# Shield_PCB.net
KiCad netlist of a schematic drawn in EAGLE
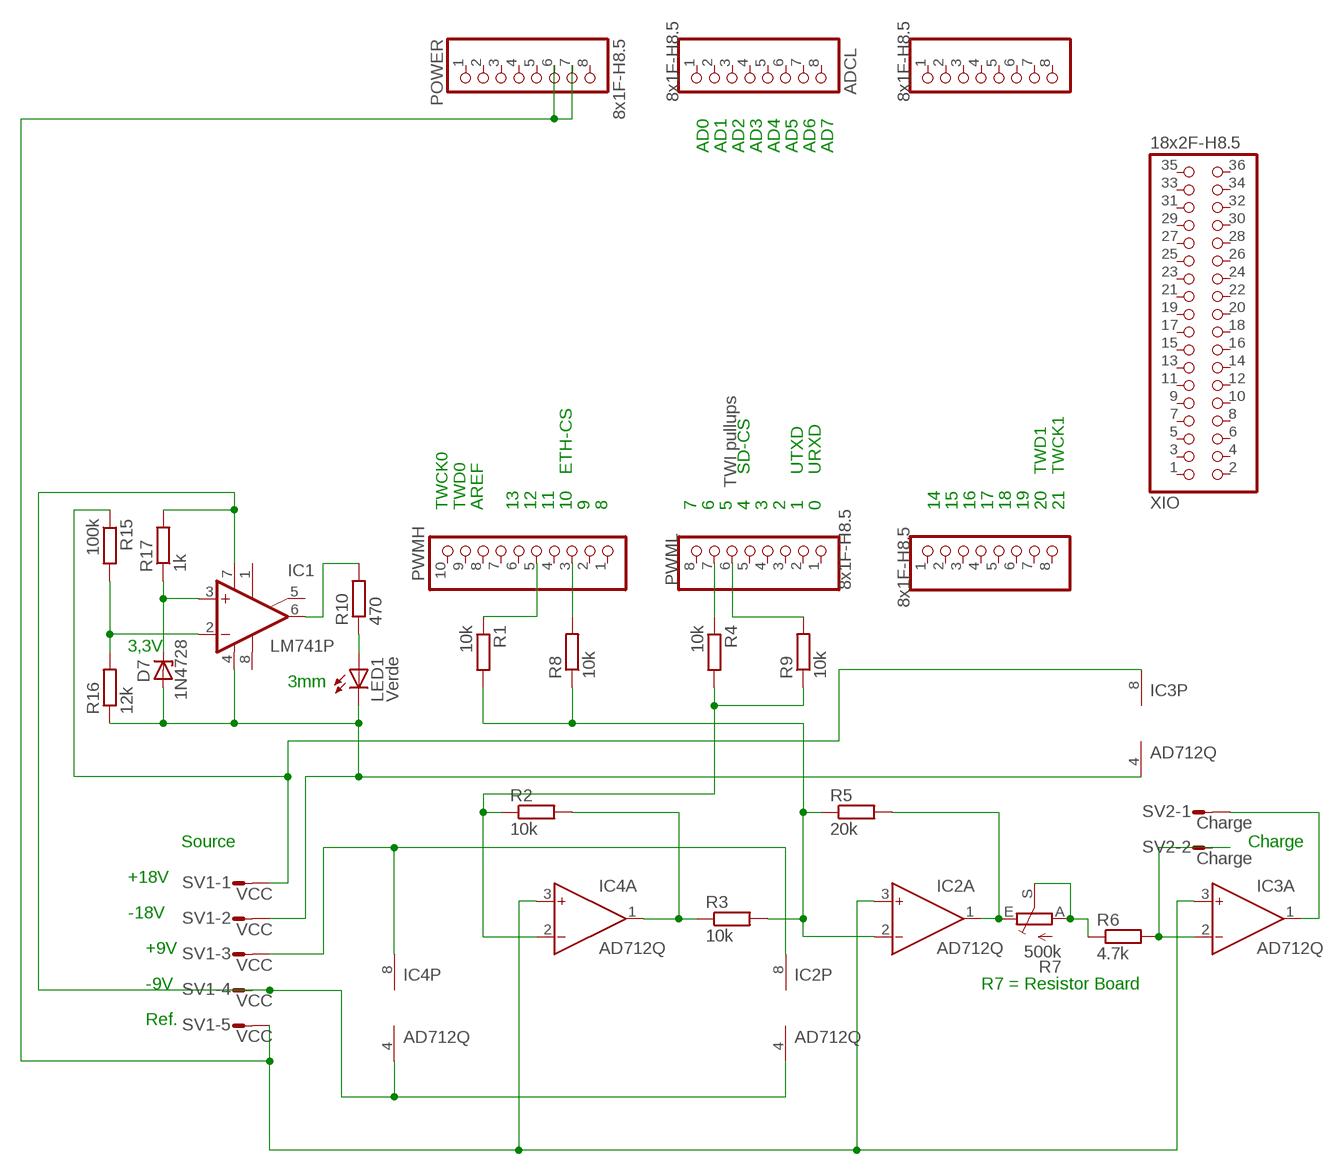
[diagram p0: schematic, sheet 1]

(export (version "E")
  (design (tool "Eeschema 10.0.6"))
  (components
    (comp (ref "ADCH")
      (value "8x1F-H8.5")
      (footprint "eagle-import:1X08")
      (libsource (lib "eagle-import") (part "PINHD-1X8"))
    )
    (comp (ref "ADCL")
      (value "8x1F-H8.5")
      (footprint "eagle-import:1X08")
      (libsource (lib "eagle-import") (part "PINHD-1X8"))
    )
    (comp (ref "COMMUNICATION")
      (value "8x1F-H8.5")
      (footprint "eagle-import:1X08")
      (libsource (lib "eagle-import") (part "PINHD-1X8"))
    )
    (comp (ref "D7")
      (value "1N4728")
      (footprint "eagle-import:DO41Z10")
      (libsource (lib "eagle-import") (part "1N4728"))
    )
    (comp (ref "IC1")
      (value "LM741P")
      (footprint "eagle-import:DIL08")
      (libsource (lib "eagle-import") (part "741PLM"))
    )
    (comp (ref "IC2")
      (value "AD712Q")
      (footprint "eagle-import:DIL08")
      (fields (field (name "MF") "ALTERA CORPORATION") (field (name "MPN") "AD712AQ"))
      (libsource (lib "eagle-import") (part "AD712Q"))
    )
    (comp (ref "IC3")
      (value "AD712Q")
      (footprint "eagle-import:DIL08")
      (fields (field (name "MF") "ALTERA CORPORATION") (field (name "MPN") "AD712AQ"))
      (libsource (lib "eagle-import") (part "AD712Q"))
    )
    (comp (ref "IC4")
      (value "AD712Q")
      (footprint "eagle-import:DIL08")
      (fields (field (name "MF") "ALTERA CORPORATION") (field (name "MPN") "AD712AQ"))
      (libsource (lib "eagle-import") (part "AD712Q"))
    )
    (comp (ref "LED1")
      (value "Verde")
      (footprint "eagle-import:LED3MM")
      (libsource (lib "eagle-import") (part "LED3MM"))
    )
    (comp (ref "POWER")
      (value "8x1F-H8.5")
      (footprint "eagle-import:1X08")
      (libsource (lib "eagle-import") (part "PINHD-1X8"))
    )
    (comp (ref "PWMH")
      (value "10x1F-H8.5")
      (footprint "eagle-import:1X10")
      (libsource (lib "eagle-import") (part "PINHD-1X10"))
    )
    (comp (ref "PWML")
      (value "8x1F-H8.5")
      (footprint "eagle-import:1X08")
      (libsource (lib "eagle-import") (part "PINHD-1X8"))
    )
    (comp (ref "R1")
      (value "10k")
      (footprint "eagle-import:0207_10")
      (libsource (lib "eagle-import") (part "resistor_R-EU_0207/10"))
    )
    (comp (ref "R2")
      (value "10k")
      (footprint "eagle-import:0207_10")
      (libsource (lib "eagle-import") (part "resistor_R-EU_0207/10"))
    )
    (comp (ref "R3")
      (value "10k")
      (footprint "eagle-import:0207_10")
      (libsource (lib "eagle-import") (part "resistor_R-EU_0207/10"))
    )
    (comp (ref "R4")
      (value "10k")
      (footprint "eagle-import:0207_10")
      (libsource (lib "eagle-import") (part "resistor_R-EU_0207/10"))
    )
    (comp (ref "R5")
      (value "20k")
      (footprint "eagle-import:0207_10")
      (libsource (lib "eagle-import") (part "resistor_R-EU_0207/10"))
    )
    (comp (ref "R6")
      (value "4.7k")
      (footprint "eagle-import:0207_10")
      (libsource (lib "eagle-import") (part "R-EU_0207/10"))
    )
    (comp (ref "R7")
      (value "500k")
      (footprint "eagle-import:B64Y")
      (libsource (lib "eagle-import") (part "TRIM_EU-B64Y"))
    )
    (comp (ref "R8")
      (value "10k")
      (footprint "eagle-import:0207_10")
      (libsource (lib "eagle-import") (part "resistor_R-EU_0207/10"))
    )
    (comp (ref "R9")
      (value "10k")
      (footprint "eagle-import:0207_10")
      (libsource (lib "eagle-import") (part "resistor_R-EU_0207/10"))
    )
    (comp (ref "R10")
      (value "470")
      (footprint "eagle-import:0207_10")
      (libsource (lib "eagle-import") (part "resistor_R-EU_0207/10"))
    )
    (comp (ref "R15")
      (value "100k")
      (footprint "eagle-import:0207_10")
      (libsource (lib "eagle-import") (part "resistor_R-EU_0207/10"))
    )
    (comp (ref "R16")
      (value "12k")
      (footprint "eagle-import:0207_10")
      (libsource (lib "eagle-import") (part "resistor_R-EU_0207/10"))
    )
    (comp (ref "R17")
      (value "1k")
      (footprint "eagle-import:0207_10")
      (libsource (lib "eagle-import") (part "resistor_R-EU_0207/10"))
    )
    (comp (ref "SV1")
      (value "VCC")
      (footprint "eagle-import:L05P")
      (libsource (lib "eagle-import") (part "L05P"))
    )
    (comp (ref "SV2")
      (value "Charge")
      (footprint "eagle-import:L02P")
      (libsource (lib "eagle-import") (part "L02P"))
    )
    (comp (ref "XIO")
      (value "18x2F-H8.5")
      (footprint "eagle-import:2X18")
      (libsource (lib "eagle-import") (part "PINHD-2X18"))
    )
  )
  (nets
    (net (code "1") (name "Net-(IC1-+IN)") (class "Default")
      (node (ref "D7") (pin "C") (pinfunction "C_C") (pintype "passive"))
      (node (ref "IC1") (pin "3") (pinfunction "+IN_3") (pintype "input"))
      (node (ref "R17") (pin "1") (pinfunction "1_1") (pintype "passive"))
    )
    (net (code "2") (name "Net-(IC1--IN)") (class "Default")
      (node (ref "IC1") (pin "2") (pinfunction "-IN_2") (pintype "input"))
      (node (ref "R15") (pin "2") (pinfunction "2_2") (pintype "passive"))
      (node (ref "R16") (pin "2") (pinfunction "2_2") (pintype "passive"))
    )
    (net (code "3") (name "Net-(IC1-OUT)") (class "Default")
      (node (ref "IC1") (pin "6") (pinfunction "OUT_6") (pintype "output"))
      (node (ref "R10") (pin "2") (pinfunction "2_2") (pintype "passive"))
    )
    (net (code "4") (name "Net-(IC1-V+)") (class "Default")
      (node (ref "IC1") (pin "7") (pinfunction "V+_7") (pintype "power_in"))
      (node (ref "IC2") (pin "4") (pinfunction "V-_4") (pintype "power_in"))
      (node (ref "IC4") (pin "4") (pinfunction "V-_4") (pintype "power_in"))
      (node (ref "R17") (pin "2") (pinfunction "2_2") (pintype "passive"))
      (node (ref "SV1") (pin "4") (pinfunction "S_4") (pintype "passive"))
    )
    (net (code "5") (name "Net-(IC1-V-)") (class "Default")
      (node (ref "D7") (pin "A") (pinfunction "A_A") (pintype "passive"))
      (node (ref "IC1") (pin "4") (pinfunction "V-_4") (pintype "power_in"))
      (node (ref "IC3") (pin "4") (pinfunction "V-_4") (pintype "power_in"))
      (node (ref "LED1") (pin "K") (pinfunction "C_K") (pintype "passive"))
      (node (ref "R16") (pin "1") (pinfunction "1_1") (pintype "passive"))
      (node (ref "SV1") (pin "2") (pinfunction "S_2") (pintype "passive"))
    )
    (net (code "6") (name "Net-(IC2A-IN+)") (class "Default")
      (node (ref "IC2") (pin "3") (pinfunction "IN+_3") (pintype "input"))
      (node (ref "IC3") (pin "3") (pinfunction "IN+_3") (pintype "input"))
      (node (ref "IC4") (pin "3") (pinfunction "IN+_3") (pintype "input"))
      (node (ref "POWER") (pin "6") (pinfunction "6_6") (pintype "passive"))
      (node (ref "POWER") (pin "7") (pinfunction "7_7") (pintype "passive"))
      (node (ref "SV1") (pin "5") (pinfunction "S_5") (pintype "passive"))
    )
    (net (code "7") (name "Net-(IC2A-IN-)") (class "Default")
      (node (ref "IC2") (pin "2") (pinfunction "IN-_2") (pintype "input"))
      (node (ref "R1") (pin "2") (pinfunction "2_2") (pintype "passive"))
      (node (ref "R3") (pin "2") (pinfunction "2_2") (pintype "passive"))
      (node (ref "R5") (pin "1") (pinfunction "1_1") (pintype "passive"))
      (node (ref "R8") (pin "1") (pinfunction "1_1") (pintype "passive"))
    )
    (net (code "8") (name "Net-(IC2A-OUT)") (class "Default")
      (node (ref "IC2") (pin "1") (pinfunction "OUT_1") (pintype "output"))
      (node (ref "R5") (pin "2") (pinfunction "2_2") (pintype "passive"))
      (node (ref "R7") (pin "E") (pinfunction "E_E") (pintype "passive"))
    )
    (net (code "9") (name "Net-(IC2C-V+)") (class "Default")
      (node (ref "IC2") (pin "8") (pinfunction "V+_8") (pintype "power_in"))
      (node (ref "IC4") (pin "8") (pinfunction "V+_8") (pintype "power_in"))
      (node (ref "SV1") (pin "3") (pinfunction "S_3") (pintype "passive"))
    )
    (net (code "10") (name "Net-(IC3A-IN-)") (class "Default")
      (node (ref "IC3") (pin "2") (pinfunction "IN-_2") (pintype "input"))
      (node (ref "R6") (pin "2") (pinfunction "2_2") (pintype "passive"))
      (node (ref "SV2") (pin "2") (pinfunction "S_2") (pintype "passive"))
    )
    (net (code "11") (name "Net-(IC3A-OUT)") (class "Default")
      (node (ref "IC3") (pin "1") (pinfunction "OUT_1") (pintype "output"))
      (node (ref "SV2") (pin "1") (pinfunction "S_1") (pintype "passive"))
    )
    (net (code "12") (name "Net-(IC3C-V+)") (class "Default")
      (node (ref "IC3") (pin "8") (pinfunction "V+_8") (pintype "power_in"))
      (node (ref "R15") (pin "1") (pinfunction "1_1") (pintype "passive"))
      (node (ref "SV1") (pin "1") (pinfunction "S_1") (pintype "passive"))
    )
    (net (code "13") (name "Net-(IC4A-IN-)") (class "Default")
      (node (ref "IC4") (pin "2") (pinfunction "IN-_2") (pintype "input"))
      (node (ref "R2") (pin "1") (pinfunction "1_1") (pintype "passive"))
      (node (ref "R4") (pin "2") (pinfunction "2_2") (pintype "passive"))
      (node (ref "R9") (pin "1") (pinfunction "1_1") (pintype "passive"))
    )
    (net (code "14") (name "Net-(IC4A-OUT)") (class "Default")
      (node (ref "IC4") (pin "1") (pinfunction "OUT_1") (pintype "output"))
      (node (ref "R2") (pin "2") (pinfunction "2_2") (pintype "passive"))
      (node (ref "R3") (pin "1") (pinfunction "1_1") (pintype "passive"))
    )
    (net (code "15") (name "Net-(LED1-PadA)") (class "Default")
      (node (ref "LED1") (pin "A") (pinfunction "A_A") (pintype "passive"))
      (node (ref "R10") (pin "1") (pinfunction "1_1") (pintype "passive"))
    )
    (net (code "16") (name "Net-(PWMH-Pad3)") (class "Default")
      (node (ref "PWMH") (pin "3") (pinfunction "3_3") (pintype "passive"))
      (node (ref "R8") (pin "2") (pinfunction "2_2") (pintype "passive"))
    )
    (net (code "17") (name "Net-(PWMH-Pad5)") (class "Default")
      (node (ref "PWMH") (pin "5") (pinfunction "5_5") (pintype "passive"))
      (node (ref "R1") (pin "1") (pinfunction "1_1") (pintype "passive"))
    )
    (net (code "18") (name "Net-(PWML-Pad6)") (class "Default")
      (node (ref "PWML") (pin "6") (pinfunction "6_6") (pintype "passive"))
      (node (ref "R9") (pin "2") (pinfunction "2_2") (pintype "passive"))
    )
    (net (code "19") (name "Net-(PWML-Pad7)") (class "Default")
      (node (ref "PWML") (pin "7") (pinfunction "7_7") (pintype "passive"))
      (node (ref "R4") (pin "1") (pinfunction "1_1") (pintype "passive"))
    )
    (net (code "20") (name "Net-(R6-Pad1)") (class "Default")
      (node (ref "R6") (pin "1") (pinfunction "1_1") (pintype "passive"))
      (node (ref "R7") (pin "A") (pinfunction "A_A") (pintype "passive"))
      (node (ref "R7") (pin "S") (pinfunction "S_S") (pintype "passive"))
    )
    (net (code "21") (name "unconnected-(ADCH-Pad1)") (class "Default")
      (node (ref "ADCH") (pin "1") (pinfunction "1_1") (pintype "passive"))
    )
    (net (code "22") (name "unconnected-(ADCH-Pad2)") (class "Default")
      (node (ref "ADCH") (pin "2") (pinfunction "2_2") (pintype "passive"))
    )
    (net (code "23") (name "unconnected-(ADCH-Pad3)") (class "Default")
      (node (ref "ADCH") (pin "3") (pinfunction "3_3") (pintype "passive"))
    )
    (net (code "24") (name "unconnected-(ADCH-Pad4)") (class "Default")
      (node (ref "ADCH") (pin "4") (pinfunction "4_4") (pintype "passive"))
    )
    (net (code "25") (name "unconnected-(ADCH-Pad5)") (class "Default")
      (node (ref "ADCH") (pin "5") (pinfunction "5_5") (pintype "passive"))
    )
    (net (code "26") (name "unconnected-(ADCH-Pad6)") (class "Default")
      (node (ref "ADCH") (pin "6") (pinfunction "6_6") (pintype "passive"))
    )
    (net (code "27") (name "unconnected-(ADCH-Pad7)") (class "Default")
      (node (ref "ADCH") (pin "7") (pinfunction "7_7") (pintype "passive"))
    )
    (net (code "28") (name "unconnected-(ADCH-Pad8)") (class "Default")
      (node (ref "ADCH") (pin "8") (pinfunction "8_8") (pintype "passive"))
    )
    (net (code "29") (name "unconnected-(ADCL-Pad1)") (class "Default")
      (node (ref "ADCL") (pin "1") (pinfunction "1_1") (pintype "passive"))
    )
    (net (code "30") (name "unconnected-(ADCL-Pad2)") (class "Default")
      (node (ref "ADCL") (pin "2") (pinfunction "2_2") (pintype "passive"))
    )
    (net (code "31") (name "unconnected-(ADCL-Pad3)") (class "Default")
      (node (ref "ADCL") (pin "3") (pinfunction "3_3") (pintype "passive"))
    )
    (net (code "32") (name "unconnected-(ADCL-Pad4)") (class "Default")
      (node (ref "ADCL") (pin "4") (pinfunction "4_4") (pintype "passive"))
    )
    (net (code "33") (name "unconnected-(ADCL-Pad5)") (class "Default")
      (node (ref "ADCL") (pin "5") (pinfunction "5_5") (pintype "passive"))
    )
    (net (code "34") (name "unconnected-(ADCL-Pad6)") (class "Default")
      (node (ref "ADCL") (pin "6") (pinfunction "6_6") (pintype "passive"))
    )
    (net (code "35") (name "unconnected-(ADCL-Pad7)") (class "Default")
      (node (ref "ADCL") (pin "7") (pinfunction "7_7") (pintype "passive"))
    )
    (net (code "36") (name "unconnected-(ADCL-Pad8)") (class "Default")
      (node (ref "ADCL") (pin "8") (pinfunction "8_8") (pintype "passive"))
    )
    (net (code "37") (name "unconnected-(COMMUNICATION-Pad1)") (class "Default")
      (node (ref "COMMUNICATION") (pin "1") (pinfunction "1_1") (pintype "passive"))
    )
    (net (code "38") (name "unconnected-(COMMUNICATION-Pad2)") (class "Default")
      (node (ref "COMMUNICATION") (pin "2") (pinfunction "2_2") (pintype "passive"))
    )
    (net (code "39") (name "unconnected-(COMMUNICATION-Pad3)") (class "Default")
      (node (ref "COMMUNICATION") (pin "3") (pinfunction "3_3") (pintype "passive"))
    )
    (net (code "40") (name "unconnected-(COMMUNICATION-Pad4)") (class "Default")
      (node (ref "COMMUNICATION") (pin "4") (pinfunction "4_4") (pintype "passive"))
    )
    (net (code "41") (name "unconnected-(COMMUNICATION-Pad5)") (class "Default")
      (node (ref "COMMUNICATION") (pin "5") (pinfunction "5_5") (pintype "passive"))
    )
    (net (code "42") (name "unconnected-(COMMUNICATION-Pad6)") (class "Default")
      (node (ref "COMMUNICATION") (pin "6") (pinfunction "6_6") (pintype "passive"))
    )
    (net (code "43") (name "unconnected-(COMMUNICATION-Pad7)") (class "Default")
      (node (ref "COMMUNICATION") (pin "7") (pinfunction "7_7") (pintype "passive"))
    )
    (net (code "44") (name "unconnected-(COMMUNICATION-Pad8)") (class "Default")
      (node (ref "COMMUNICATION") (pin "8") (pinfunction "8_8") (pintype "passive"))
    )
    (net (code "45") (name "unconnected-(IC1-ON1-Pad1)") (class "Default")
      (node (ref "IC1") (pin "1") (pinfunction "ON1_1") (pintype "passive"))
    )
    (net (code "46") (name "unconnected-(IC1-ON2-Pad5)") (class "Default")
      (node (ref "IC1") (pin "5") (pinfunction "ON2_5") (pintype "passive"))
    )
    (net (code "47") (name "unconnected-(IC1-OPT-Pad8)") (class "Default")
      (node (ref "IC1") (pin "8") (pinfunction "OPT_8") (pintype "passive"))
    )
    (net (code "48") (name "unconnected-(POWER-Pad1)") (class "Default")
      (node (ref "POWER") (pin "1") (pinfunction "1_1") (pintype "passive"))
    )
    (net (code "49") (name "unconnected-(POWER-Pad2)") (class "Default")
      (node (ref "POWER") (pin "2") (pinfunction "2_2") (pintype "passive"))
    )
    (net (code "50") (name "unconnected-(POWER-Pad3)") (class "Default")
      (node (ref "POWER") (pin "3") (pinfunction "3_3") (pintype "passive"))
    )
    (net (code "51") (name "unconnected-(POWER-Pad4)") (class "Default")
      (node (ref "POWER") (pin "4") (pinfunction "4_4") (pintype "passive"))
    )
    (net (code "52") (name "unconnected-(POWER-Pad5)") (class "Default")
      (node (ref "POWER") (pin "5") (pinfunction "5_5") (pintype "passive"))
    )
    (net (code "53") (name "unconnected-(POWER-Pad8)") (class "Default")
      (node (ref "POWER") (pin "8") (pinfunction "8_8") (pintype "passive"))
    )
    (net (code "54") (name "unconnected-(PWMH-Pad1)") (class "Default")
      (node (ref "PWMH") (pin "1") (pinfunction "1_1") (pintype "passive"))
    )
    (net (code "55") (name "unconnected-(PWMH-Pad2)") (class "Default")
      (node (ref "PWMH") (pin "2") (pinfunction "2_2") (pintype "passive"))
    )
    (net (code "56") (name "unconnected-(PWMH-Pad4)") (class "Default")
      (node (ref "PWMH") (pin "4") (pinfunction "4_4") (pintype "passive"))
    )
    (net (code "57") (name "unconnected-(PWMH-Pad6)") (class "Default")
      (node (ref "PWMH") (pin "6") (pinfunction "6_6") (pintype "passive"))
    )
    (net (code "58") (name "unconnected-(PWMH-Pad7)") (class "Default")
      (node (ref "PWMH") (pin "7") (pinfunction "7_7") (pintype "passive"))
    )
    (net (code "59") (name "unconnected-(PWMH-Pad8)") (class "Default")
      (node (ref "PWMH") (pin "8") (pinfunction "8_8") (pintype "passive"))
    )
    (net (code "60") (name "unconnected-(PWMH-Pad9)") (class "Default")
      (node (ref "PWMH") (pin "9") (pinfunction "9_9") (pintype "passive"))
    )
    (net (code "61") (name "unconnected-(PWMH-Pad10)") (class "Default")
      (node (ref "PWMH") (pin "10") (pinfunction "10_10") (pintype "passive"))
    )
    (net (code "62") (name "unconnected-(PWML-Pad1)") (class "Default")
      (node (ref "PWML") (pin "1") (pinfunction "1_1") (pintype "passive"))
    )
    (net (code "63") (name "unconnected-(PWML-Pad2)") (class "Default")
      (node (ref "PWML") (pin "2") (pinfunction "2_2") (pintype "passive"))
    )
    (net (code "64") (name "unconnected-(PWML-Pad3)") (class "Default")
      (node (ref "PWML") (pin "3") (pinfunction "3_3") (pintype "passive"))
    )
    (net (code "65") (name "unconnected-(PWML-Pad4)") (class "Default")
      (node (ref "PWML") (pin "4") (pinfunction "4_4") (pintype "passive"))
    )
    (net (code "66") (name "unconnected-(PWML-Pad5)") (class "Default")
      (node (ref "PWML") (pin "5") (pinfunction "5_5") (pintype "passive"))
    )
    (net (code "67") (name "unconnected-(PWML-Pad8)") (class "Default")
      (node (ref "PWML") (pin "8") (pinfunction "8_8") (pintype "passive"))
    )
    (net (code "68") (name "unconnected-(XIO-Pad1)") (class "Default")
      (node (ref "XIO") (pin "1") (pinfunction "1_1") (pintype "passive"))
    )
    (net (code "69") (name "unconnected-(XIO-Pad2)") (class "Default")
      (node (ref "XIO") (pin "2") (pinfunction "2_2") (pintype "passive"))
    )
    (net (code "70") (name "unconnected-(XIO-Pad3)") (class "Default")
      (node (ref "XIO") (pin "3") (pinfunction "3_3") (pintype "passive"))
    )
    (net (code "71") (name "unconnected-(XIO-Pad4)") (class "Default")
      (node (ref "XIO") (pin "4") (pinfunction "4_4") (pintype "passive"))
    )
    (net (code "72") (name "unconnected-(XIO-Pad5)") (class "Default")
      (node (ref "XIO") (pin "5") (pinfunction "5_5") (pintype "passive"))
    )
    (net (code "73") (name "unconnected-(XIO-Pad6)") (class "Default")
      (node (ref "XIO") (pin "6") (pinfunction "6_6") (pintype "passive"))
    )
    (net (code "74") (name "unconnected-(XIO-Pad7)") (class "Default")
      (node (ref "XIO") (pin "7") (pinfunction "7_7") (pintype "passive"))
    )
    (net (code "75") (name "unconnected-(XIO-Pad8)") (class "Default")
      (node (ref "XIO") (pin "8") (pinfunction "8_8") (pintype "passive"))
    )
    (net (code "76") (name "unconnected-(XIO-Pad9)") (class "Default")
      (node (ref "XIO") (pin "9") (pinfunction "9_9") (pintype "passive"))
    )
    (net (code "77") (name "unconnected-(XIO-Pad10)") (class "Default")
      (node (ref "XIO") (pin "10") (pinfunction "10_10") (pintype "passive"))
    )
    (net (code "78") (name "unconnected-(XIO-Pad11)") (class "Default")
      (node (ref "XIO") (pin "11") (pinfunction "11_11") (pintype "passive"))
    )
    (net (code "79") (name "unconnected-(XIO-Pad12)") (class "Default")
      (node (ref "XIO") (pin "12") (pinfunction "12_12") (pintype "passive"))
    )
    (net (code "80") (name "unconnected-(XIO-Pad13)") (class "Default")
      (node (ref "XIO") (pin "13") (pinfunction "13_13") (pintype "passive"))
    )
    (net (code "81") (name "unconnected-(XIO-Pad14)") (class "Default")
      (node (ref "XIO") (pin "14") (pinfunction "14_14") (pintype "passive"))
    )
    (net (code "82") (name "unconnected-(XIO-Pad15)") (class "Default")
      (node (ref "XIO") (pin "15") (pinfunction "15_15") (pintype "passive"))
    )
    (net (code "83") (name "unconnected-(XIO-Pad16)") (class "Default")
      (node (ref "XIO") (pin "16") (pinfunction "16_16") (pintype "passive"))
    )
    (net (code "84") (name "unconnected-(XIO-Pad17)") (class "Default")
      (node (ref "XIO") (pin "17") (pinfunction "17_17") (pintype "passive"))
    )
    (net (code "85") (name "unconnected-(XIO-Pad18)") (class "Default")
      (node (ref "XIO") (pin "18") (pinfunction "18_18") (pintype "passive"))
    )
    (net (code "86") (name "unconnected-(XIO-Pad19)") (class "Default")
      (node (ref "XIO") (pin "19") (pinfunction "19_19") (pintype "passive"))
    )
    (net (code "87") (name "unconnected-(XIO-Pad20)") (class "Default")
      (node (ref "XIO") (pin "20") (pinfunction "20_20") (pintype "passive"))
    )
    (net (code "88") (name "unconnected-(XIO-Pad21)") (class "Default")
      (node (ref "XIO") (pin "21") (pinfunction "21_21") (pintype "passive"))
    )
    (net (code "89") (name "unconnected-(XIO-Pad22)") (class "Default")
      (node (ref "XIO") (pin "22") (pinfunction "22_22") (pintype "passive"))
    )
    (net (code "90") (name "unconnected-(XIO-Pad23)") (class "Default")
      (node (ref "XIO") (pin "23") (pinfunction "23_23") (pintype "passive"))
    )
    (net (code "91") (name "unconnected-(XIO-Pad24)") (class "Default")
      (node (ref "XIO") (pin "24") (pinfunction "24_24") (pintype "passive"))
    )
    (net (code "92") (name "unconnected-(XIO-Pad25)") (class "Default")
      (node (ref "XIO") (pin "25") (pinfunction "25_25") (pintype "passive"))
    )
    (net (code "93") (name "unconnected-(XIO-Pad26)") (class "Default")
      (node (ref "XIO") (pin "26") (pinfunction "26_26") (pintype "passive"))
    )
    (net (code "94") (name "unconnected-(XIO-Pad27)") (class "Default")
      (node (ref "XIO") (pin "27") (pinfunction "27_27") (pintype "passive"))
    )
    (net (code "95") (name "unconnected-(XIO-Pad28)") (class "Default")
      (node (ref "XIO") (pin "28") (pinfunction "28_28") (pintype "passive"))
    )
    (net (code "96") (name "unconnected-(XIO-Pad29)") (class "Default")
      (node (ref "XIO") (pin "29") (pinfunction "29_29") (pintype "passive"))
    )
    (net (code "97") (name "unconnected-(XIO-Pad30)") (class "Default")
      (node (ref "XIO") (pin "30") (pinfunction "30_30") (pintype "passive"))
    )
    (net (code "98") (name "unconnected-(XIO-Pad31)") (class "Default")
      (node (ref "XIO") (pin "31") (pinfunction "31_31") (pintype "passive"))
    )
    (net (code "99") (name "unconnected-(XIO-Pad32)") (class "Default")
      (node (ref "XIO") (pin "32") (pinfunction "32_32") (pintype "passive"))
    )
    (net (code "100") (name "unconnected-(XIO-Pad33)") (class "Default")
      (node (ref "XIO") (pin "33") (pinfunction "33_33") (pintype "passive"))
    )
    (net (code "101") (name "unconnected-(XIO-Pad34)") (class "Default")
      (node (ref "XIO") (pin "34") (pinfunction "34_34") (pintype "passive"))
    )
    (net (code "102") (name "unconnected-(XIO-Pad35)") (class "Default")
      (node (ref "XIO") (pin "35") (pinfunction "35_35") (pintype "passive"))
    )
    (net (code "103") (name "unconnected-(XIO-Pad36)") (class "Default")
      (node (ref "XIO") (pin "36") (pinfunction "36_36") (pintype "passive"))
    )
  )
)
